# STM32F103RBT6_2.net
KiCad netlist of a schematic drawn in Altium Designer
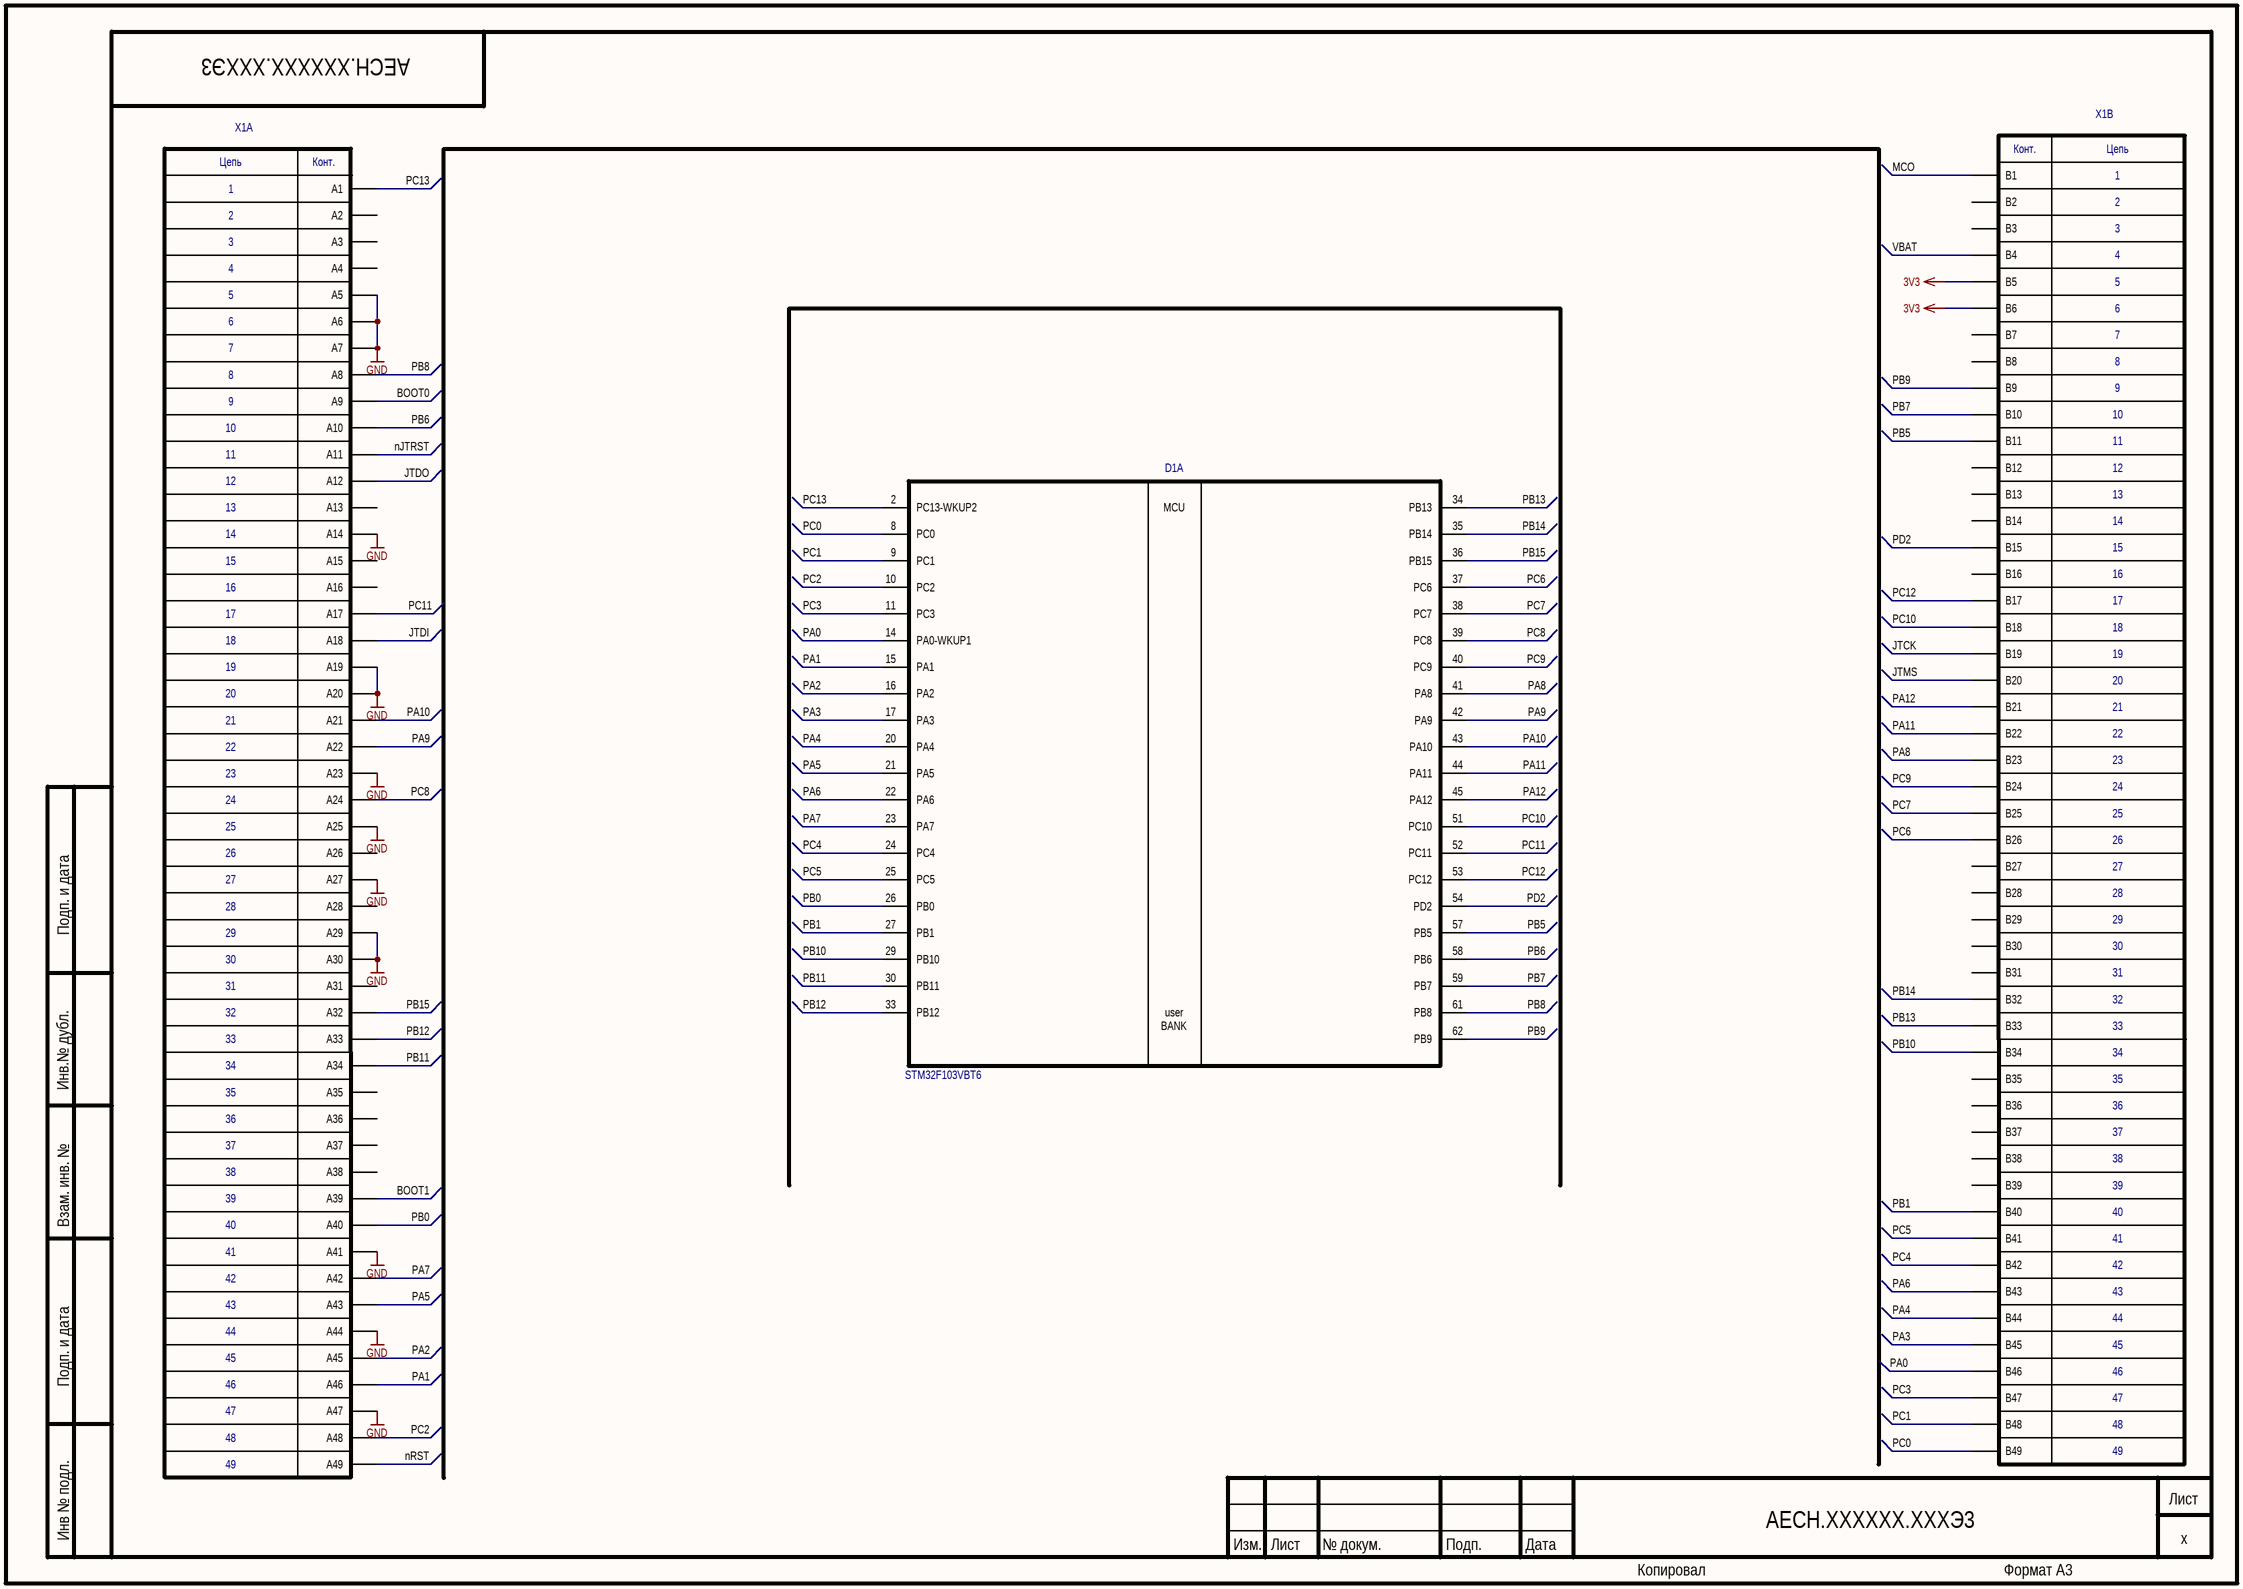
[diagram p0: Модуль STM32F103RBT6_2.SchDoc]

(export (version "E")
  (design (tool "Eeschema 10.0.6"))
  (components
    (comp (ref "D1")
      (value "STM32F103VBT6")
      (footprint "QFP50P1200X1200X160-64N")
      (fields (field (name "Comment") " (LQFP-48) Xilinx"))
      (libsource (lib "Lisaveta_SCH") (part "STM32F103RBT6"))
    )
    (comp (ref "X1")
      (value "KONT_POLE_MEZ")
      (footprint "3113-112t_otv")
      (libsource (lib "Lisaveta_SCH") (part "3113-112T"))
    )
  )
  (nets
    (net (code "1") (name "/BOOT0") (class "Default")
      (node (ref "X1") (pin "A9") (pinfunction "A9_A9") (pintype "passive"))
    )
    (net (code "2") (name "/BOOT1") (class "Default")
      (node (ref "X1") (pin "A39") (pinfunction "A39_A39") (pintype "passive"))
    )
    (net (code "3") (name "/JTCK") (class "Default")
      (node (ref "X1") (pin "B19") (pinfunction "B19_B19") (pintype "passive"))
    )
    (net (code "4") (name "/JTDI") (class "Default")
      (node (ref "X1") (pin "A18") (pinfunction "A18_A18") (pintype "passive"))
    )
    (net (code "5") (name "/JTDO") (class "Default")
      (node (ref "X1") (pin "A12") (pinfunction "A12_A12") (pintype "passive"))
    )
    (net (code "6") (name "/JTMS") (class "Default")
      (node (ref "X1") (pin "B20") (pinfunction "B20_B20") (pintype "passive"))
    )
    (net (code "7") (name "/MCO") (class "Default")
      (node (ref "X1") (pin "B1") (pinfunction "B1_B1") (pintype "passive"))
    )
    (net (code "8") (name "/PA0") (class "Default")
      (node (ref "D1") (pin "14") (pinfunction "PA0-WKUP1_14") (pintype "passive"))
      (node (ref "X1") (pin "B46") (pinfunction "B46_B46") (pintype "passive"))
    )
    (net (code "9") (name "/PA1") (class "Default")
      (node (ref "D1") (pin "15") (pinfunction "PA1_15") (pintype "passive"))
      (node (ref "X1") (pin "A46") (pinfunction "A46_A46") (pintype "passive"))
    )
    (net (code "10") (name "/PA2") (class "Default")
      (node (ref "D1") (pin "16") (pinfunction "PA2_16") (pintype "passive"))
      (node (ref "X1") (pin "A45") (pinfunction "A45_A45") (pintype "passive"))
    )
    (net (code "11") (name "/PA3") (class "Default")
      (node (ref "D1") (pin "17") (pinfunction "PA3_17") (pintype "passive"))
      (node (ref "X1") (pin "B45") (pinfunction "B45_B45") (pintype "passive"))
    )
    (net (code "12") (name "/PA4") (class "Default")
      (node (ref "D1") (pin "20") (pinfunction "PA4_20") (pintype "passive"))
      (node (ref "X1") (pin "B44") (pinfunction "B44_B44") (pintype "passive"))
    )
    (net (code "13") (name "/PA5") (class "Default")
      (node (ref "D1") (pin "21") (pinfunction "PA5_21") (pintype "passive"))
      (node (ref "X1") (pin "A43") (pinfunction "A43_A43") (pintype "passive"))
    )
    (net (code "14") (name "/PA6") (class "Default")
      (node (ref "D1") (pin "22") (pinfunction "PA6_22") (pintype "passive"))
      (node (ref "X1") (pin "B43") (pinfunction "B43_B43") (pintype "passive"))
    )
    (net (code "15") (name "/PA7") (class "Default")
      (node (ref "D1") (pin "23") (pinfunction "PA7_23") (pintype "passive"))
      (node (ref "X1") (pin "A42") (pinfunction "A42_A42") (pintype "passive"))
    )
    (net (code "16") (name "/PA8") (class "Default")
      (node (ref "D1") (pin "41") (pinfunction "PA8_41") (pintype "passive"))
      (node (ref "X1") (pin "B23") (pinfunction "B23_B23") (pintype "passive"))
    )
    (net (code "17") (name "/PA9") (class "Default")
      (node (ref "D1") (pin "42") (pinfunction "PA9_42") (pintype "passive"))
      (node (ref "X1") (pin "A22") (pinfunction "A22_A22") (pintype "passive"))
    )
    (net (code "18") (name "/PA10") (class "Default")
      (node (ref "D1") (pin "43") (pinfunction "PA10_43") (pintype "passive"))
      (node (ref "X1") (pin "A21") (pinfunction "A21_A21") (pintype "passive"))
    )
    (net (code "19") (name "/PA11") (class "Default")
      (node (ref "D1") (pin "44") (pinfunction "PA11_44") (pintype "passive"))
      (node (ref "X1") (pin "B22") (pinfunction "B22_B22") (pintype "passive"))
    )
    (net (code "20") (name "/PA12") (class "Default")
      (node (ref "D1") (pin "45") (pinfunction "PA12_45") (pintype "passive"))
      (node (ref "X1") (pin "B21") (pinfunction "B21_B21") (pintype "passive"))
    )
    (net (code "21") (name "/PB0") (class "Default")
      (node (ref "D1") (pin "26") (pinfunction "PB0_26") (pintype "passive"))
      (node (ref "X1") (pin "A40") (pinfunction "A40_A40") (pintype "passive"))
    )
    (net (code "22") (name "/PB1") (class "Default")
      (node (ref "D1") (pin "27") (pinfunction "PB1_27") (pintype "passive"))
      (node (ref "X1") (pin "B40") (pinfunction "B40_B40") (pintype "passive"))
    )
    (net (code "23") (name "/PB5") (class "Default")
      (node (ref "D1") (pin "57") (pinfunction "PB5_57") (pintype "passive"))
      (node (ref "X1") (pin "B11") (pinfunction "B11_B11") (pintype "passive"))
    )
    (net (code "24") (name "/PB6") (class "Default")
      (node (ref "D1") (pin "58") (pinfunction "PB6_58") (pintype "passive"))
      (node (ref "X1") (pin "A10") (pinfunction "A10_A10") (pintype "passive"))
    )
    (net (code "25") (name "/PB7") (class "Default")
      (node (ref "D1") (pin "59") (pinfunction "PB7_59") (pintype "passive"))
      (node (ref "X1") (pin "B10") (pinfunction "B10_B10") (pintype "passive"))
    )
    (net (code "26") (name "/PB8") (class "Default")
      (node (ref "D1") (pin "61") (pinfunction "PB8_61") (pintype "passive"))
      (node (ref "X1") (pin "A8") (pinfunction "A8_A8") (pintype "passive"))
    )
    (net (code "27") (name "/PB9") (class "Default")
      (node (ref "D1") (pin "62") (pinfunction "PB9_62") (pintype "passive"))
      (node (ref "X1") (pin "B9") (pinfunction "B9_B9") (pintype "passive"))
    )
    (net (code "28") (name "/PB10") (class "Default")
      (node (ref "D1") (pin "29") (pinfunction "PB10_29") (pintype "passive"))
      (node (ref "X1") (pin "B34") (pinfunction "B34_B34") (pintype "passive"))
    )
    (net (code "29") (name "/PB11") (class "Default")
      (node (ref "D1") (pin "30") (pinfunction "PB11_30") (pintype "passive"))
      (node (ref "X1") (pin "A34") (pinfunction "A34_A34") (pintype "passive"))
    )
    (net (code "30") (name "/PB12") (class "Default")
      (node (ref "D1") (pin "33") (pinfunction "PB12_33") (pintype "passive"))
      (node (ref "X1") (pin "A33") (pinfunction "A33_A33") (pintype "passive"))
    )
    (net (code "31") (name "/PB13") (class "Default")
      (node (ref "D1") (pin "34") (pinfunction "PB13_34") (pintype "passive"))
      (node (ref "X1") (pin "B33") (pinfunction "B33_B33") (pintype "passive"))
    )
    (net (code "32") (name "/PB14") (class "Default")
      (node (ref "D1") (pin "35") (pinfunction "PB14_35") (pintype "passive"))
      (node (ref "X1") (pin "B32") (pinfunction "B32_B32") (pintype "passive"))
    )
    (net (code "33") (name "/PB15") (class "Default")
      (node (ref "D1") (pin "36") (pinfunction "PB15_36") (pintype "passive"))
      (node (ref "X1") (pin "A32") (pinfunction "A32_A32") (pintype "passive"))
    )
    (net (code "34") (name "/PC0") (class "Default")
      (node (ref "D1") (pin "8") (pinfunction "PC0_8") (pintype "passive"))
      (node (ref "X1") (pin "B49") (pinfunction "B49_B49") (pintype "passive"))
    )
    (net (code "35") (name "/PC1") (class "Default")
      (node (ref "D1") (pin "9") (pinfunction "PC1_9") (pintype "passive"))
      (node (ref "X1") (pin "B48") (pinfunction "B48_B48") (pintype "passive"))
    )
    (net (code "36") (name "/PC2") (class "Default")
      (node (ref "D1") (pin "10") (pinfunction "PC2_10") (pintype "passive"))
      (node (ref "X1") (pin "A48") (pinfunction "A48_A48") (pintype "passive"))
    )
    (net (code "37") (name "/PC3") (class "Default")
      (node (ref "D1") (pin "11") (pinfunction "PC3_11") (pintype "passive"))
      (node (ref "X1") (pin "B47") (pinfunction "B47_B47") (pintype "passive"))
    )
    (net (code "38") (name "/PC4") (class "Default")
      (node (ref "D1") (pin "24") (pinfunction "PC4_24") (pintype "passive"))
      (node (ref "X1") (pin "B42") (pinfunction "B42_B42") (pintype "passive"))
    )
    (net (code "39") (name "/PC5") (class "Default")
      (node (ref "D1") (pin "25") (pinfunction "PC5_25") (pintype "passive"))
      (node (ref "X1") (pin "B41") (pinfunction "B41_B41") (pintype "passive"))
    )
    (net (code "40") (name "/PC6") (class "Default")
      (node (ref "D1") (pin "37") (pinfunction "PC6_37") (pintype "passive"))
      (node (ref "X1") (pin "B26") (pinfunction "B26_B26") (pintype "passive"))
    )
    (net (code "41") (name "/PC7") (class "Default")
      (node (ref "D1") (pin "38") (pinfunction "PC7_38") (pintype "passive"))
      (node (ref "X1") (pin "B25") (pinfunction "B25_B25") (pintype "passive"))
    )
    (net (code "42") (name "/PC8") (class "Default")
      (node (ref "D1") (pin "39") (pinfunction "PC8_39") (pintype "passive"))
      (node (ref "X1") (pin "A24") (pinfunction "A24_A24") (pintype "passive"))
    )
    (net (code "43") (name "/PC9") (class "Default")
      (node (ref "D1") (pin "40") (pinfunction "PC9_40") (pintype "passive"))
      (node (ref "X1") (pin "B24") (pinfunction "B24_B24") (pintype "passive"))
    )
    (net (code "44") (name "/PC10") (class "Default")
      (node (ref "D1") (pin "51") (pinfunction "PC10_51") (pintype "passive"))
      (node (ref "X1") (pin "B18") (pinfunction "B18_B18") (pintype "passive"))
    )
    (net (code "45") (name "/PC11") (class "Default")
      (node (ref "D1") (pin "52") (pinfunction "PC11_52") (pintype "passive"))
      (node (ref "X1") (pin "A17") (pinfunction "A17_A17") (pintype "passive"))
    )
    (net (code "46") (name "/PC12") (class "Default")
      (node (ref "D1") (pin "53") (pinfunction "PC12_53") (pintype "passive"))
      (node (ref "X1") (pin "B17") (pinfunction "B17_B17") (pintype "passive"))
    )
    (net (code "47") (name "/PC13") (class "Default")
      (node (ref "D1") (pin "2") (pinfunction "PC13-WKUP2_2") (pintype "passive"))
      (node (ref "X1") (pin "A1") (pinfunction "A1_A1") (pintype "passive"))
    )
    (net (code "48") (name "/PD2") (class "Default")
      (node (ref "D1") (pin "54") (pinfunction "PD2_54") (pintype "passive"))
      (node (ref "X1") (pin "B15") (pinfunction "B15_B15") (pintype "passive"))
    )
    (net (code "49") (name "/VBAT") (class "Default")
      (node (ref "X1") (pin "B4") (pinfunction "B4_B4") (pintype "passive"))
    )
    (net (code "50") (name "/nJTRST") (class "Default")
      (node (ref "X1") (pin "A11") (pinfunction "A11_A11") (pintype "passive"))
    )
    (net (code "51") (name "/nRST") (class "Default")
      (node (ref "X1") (pin "A49") (pinfunction "A49_A49") (pintype "passive"))
    )
    (net (code "52") (name "3V3") (class "Default")
      (node (ref "X1") (pin "B5") (pinfunction "B5_B5") (pintype "passive"))
      (node (ref "X1") (pin "B6") (pinfunction "B6_B6") (pintype "passive"))
    )
    (net (code "53") (name "GND") (class "Default")
      (node (ref "X1") (pin "A14") (pinfunction "A14_A14") (pintype "passive"))
      (node (ref "X1") (pin "A19") (pinfunction "A19_A19") (pintype "passive"))
      (node (ref "X1") (pin "A20") (pinfunction "A20_A20") (pintype "passive"))
      (node (ref "X1") (pin "A23") (pinfunction "A23_A23") (pintype "passive"))
      (node (ref "X1") (pin "A25") (pinfunction "A25_A25") (pintype "passive"))
      (node (ref "X1") (pin "A27") (pinfunction "A27_A27") (pintype "passive"))
      (node (ref "X1") (pin "A29") (pinfunction "A29_A29") (pintype "passive"))
      (node (ref "X1") (pin "A30") (pinfunction "A30_A30") (pintype "passive"))
      (node (ref "X1") (pin "A41") (pinfunction "A41_A41") (pintype "passive"))
      (node (ref "X1") (pin "A44") (pinfunction "A44_A44") (pintype "passive"))
      (node (ref "X1") (pin "A47") (pinfunction "A47_A47") (pintype "passive"))
      (node (ref "X1") (pin "A5") (pinfunction "A5_A5") (pintype "passive"))
      (node (ref "X1") (pin "A6") (pinfunction "A6_A6") (pintype "passive"))
      (node (ref "X1") (pin "A7") (pinfunction "A7_A7") (pintype "passive"))
    )
    (net (code "54") (name "unconnected-(X1-PadA2)") (class "Default")
      (node (ref "X1") (pin "A2") (pinfunction "A2_A2") (pintype "passive"))
    )
    (net (code "55") (name "unconnected-(X1-PadA3)") (class "Default")
      (node (ref "X1") (pin "A3") (pinfunction "A3_A3") (pintype "passive"))
    )
    (net (code "56") (name "unconnected-(X1-PadA4)") (class "Default")
      (node (ref "X1") (pin "A4") (pinfunction "A4_A4") (pintype "passive"))
    )
    (net (code "57") (name "unconnected-(X1-PadA13)") (class "Default")
      (node (ref "X1") (pin "A13") (pinfunction "A13_A13") (pintype "passive"))
    )
    (net (code "58") (name "unconnected-(X1-PadA15)") (class "Default")
      (node (ref "X1") (pin "A15") (pinfunction "A15_A15") (pintype "passive"))
    )
    (net (code "59") (name "unconnected-(X1-PadA16)") (class "Default")
      (node (ref "X1") (pin "A16") (pinfunction "A16_A16") (pintype "passive"))
    )
    (net (code "60") (name "unconnected-(X1-PadA26)") (class "Default")
      (node (ref "X1") (pin "A26") (pinfunction "A26_A26") (pintype "passive"))
    )
    (net (code "61") (name "unconnected-(X1-PadA28)") (class "Default")
      (node (ref "X1") (pin "A28") (pinfunction "A28_A28") (pintype "passive"))
    )
    (net (code "62") (name "unconnected-(X1-PadA31)") (class "Default")
      (node (ref "X1") (pin "A31") (pinfunction "A31_A31") (pintype "passive"))
    )
    (net (code "63") (name "unconnected-(X1-PadA35)") (class "Default")
      (node (ref "X1") (pin "A35") (pinfunction "A35_A35") (pintype "passive"))
    )
    (net (code "64") (name "unconnected-(X1-PadA36)") (class "Default")
      (node (ref "X1") (pin "A36") (pinfunction "A36_A36") (pintype "passive"))
    )
    (net (code "65") (name "unconnected-(X1-PadA37)") (class "Default")
      (node (ref "X1") (pin "A37") (pinfunction "A37_A37") (pintype "passive"))
    )
    (net (code "66") (name "unconnected-(X1-PadA38)") (class "Default")
      (node (ref "X1") (pin "A38") (pinfunction "A38_A38") (pintype "passive"))
    )
    (net (code "67") (name "unconnected-(X1-PadB2)") (class "Default")
      (node (ref "X1") (pin "B2") (pinfunction "B2_B2") (pintype "passive"))
    )
    (net (code "68") (name "unconnected-(X1-PadB3)") (class "Default")
      (node (ref "X1") (pin "B3") (pinfunction "B3_B3") (pintype "passive"))
    )
    (net (code "69") (name "unconnected-(X1-PadB7)") (class "Default")
      (node (ref "X1") (pin "B7") (pinfunction "B7_B7") (pintype "passive"))
    )
    (net (code "70") (name "unconnected-(X1-PadB8)") (class "Default")
      (node (ref "X1") (pin "B8") (pinfunction "B8_B8") (pintype "passive"))
    )
    (net (code "71") (name "unconnected-(X1-PadB12)") (class "Default")
      (node (ref "X1") (pin "B12") (pinfunction "B12_B12") (pintype "passive"))
    )
    (net (code "72") (name "unconnected-(X1-PadB13)") (class "Default")
      (node (ref "X1") (pin "B13") (pinfunction "B13_B13") (pintype "passive"))
    )
    (net (code "73") (name "unconnected-(X1-PadB14)") (class "Default")
      (node (ref "X1") (pin "B14") (pinfunction "B14_B14") (pintype "passive"))
    )
    (net (code "74") (name "unconnected-(X1-PadB16)") (class "Default")
      (node (ref "X1") (pin "B16") (pinfunction "B16_B16") (pintype "passive"))
    )
    (net (code "75") (name "unconnected-(X1-PadB27)") (class "Default")
      (node (ref "X1") (pin "B27") (pinfunction "B27_B27") (pintype "passive"))
    )
    (net (code "76") (name "unconnected-(X1-PadB28)") (class "Default")
      (node (ref "X1") (pin "B28") (pinfunction "B28_B28") (pintype "passive"))
    )
    (net (code "77") (name "unconnected-(X1-PadB29)") (class "Default")
      (node (ref "X1") (pin "B29") (pinfunction "B29_B29") (pintype "passive"))
    )
    (net (code "78") (name "unconnected-(X1-PadB30)") (class "Default")
      (node (ref "X1") (pin "B30") (pinfunction "B30_B30") (pintype "passive"))
    )
    (net (code "79") (name "unconnected-(X1-PadB31)") (class "Default")
      (node (ref "X1") (pin "B31") (pinfunction "B31_B31") (pintype "passive"))
    )
    (net (code "80") (name "unconnected-(X1-PadB35)") (class "Default")
      (node (ref "X1") (pin "B35") (pinfunction "B35_B35") (pintype "passive"))
    )
    (net (code "81") (name "unconnected-(X1-PadB36)") (class "Default")
      (node (ref "X1") (pin "B36") (pinfunction "B36_B36") (pintype "passive"))
    )
    (net (code "82") (name "unconnected-(X1-PadB37)") (class "Default")
      (node (ref "X1") (pin "B37") (pinfunction "B37_B37") (pintype "passive"))
    )
    (net (code "83") (name "unconnected-(X1-PadB38)") (class "Default")
      (node (ref "X1") (pin "B38") (pinfunction "B38_B38") (pintype "passive"))
    )
    (net (code "84") (name "unconnected-(X1-PadB39)") (class "Default")
      (node (ref "X1") (pin "B39") (pinfunction "B39_B39") (pintype "passive"))
    )
  )
)
